# Adapter6.net
KiCad netlist of a schematic drawn in EAGLE
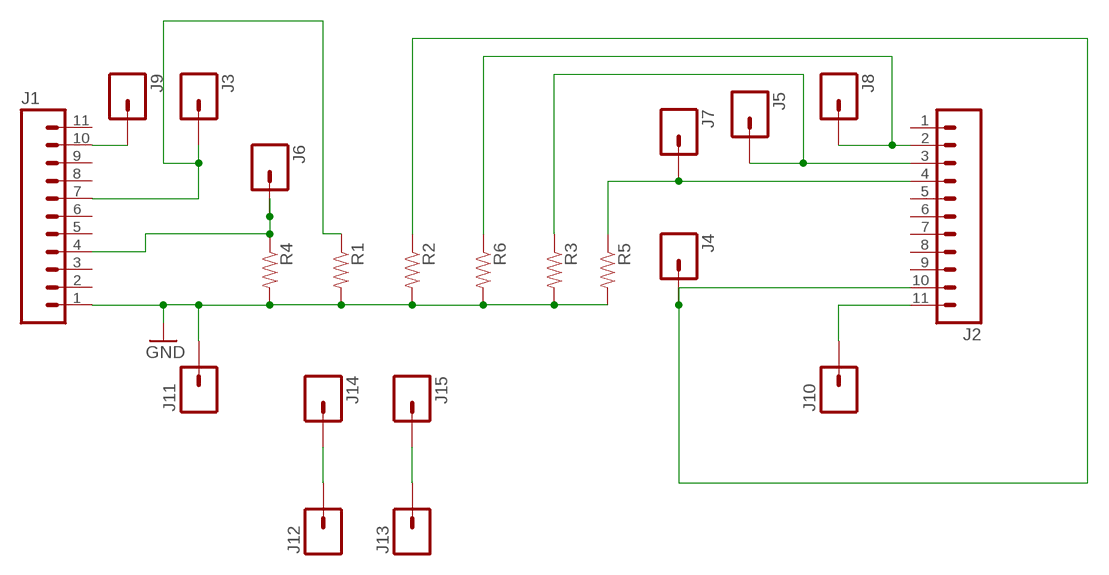
[diagram p0: schematic, sheet 1]

(export (version "E")
  (design (tool "Eeschema 10.0.6"))
  (components
    (comp (ref "J1")
      (value "M11PTH")
      (footprint "eagle-import:1X11")
      (libsource (lib "eagle-import") (part "M11PTH"))
    )
    (comp (ref "J2")
      (value "M11PTH")
      (footprint "eagle-import:1X11")
      (libsource (lib "eagle-import") (part "M11PTH"))
    )
    (comp (ref "J3")
      (value "M01PTH_2MM")
      (footprint "eagle-import:1X01_2MM")
      (libsource (lib "eagle-import") (part "M01PTH_2MM"))
    )
    (comp (ref "J4")
      (value "M01PTH_2MM")
      (footprint "eagle-import:1X01_2MM")
      (libsource (lib "eagle-import") (part "M01PTH_2MM"))
    )
    (comp (ref "J5")
      (value "M01PTH_2MM")
      (footprint "eagle-import:1X01_2MM")
      (libsource (lib "eagle-import") (part "M01PTH_2MM"))
    )
    (comp (ref "J6")
      (value "M01PTH_2MM")
      (footprint "eagle-import:1X01_2MM")
      (libsource (lib "eagle-import") (part "M01PTH_2MM"))
    )
    (comp (ref "J7")
      (value "M01PTH_2MM")
      (footprint "eagle-import:1X01_2MM")
      (libsource (lib "eagle-import") (part "M01PTH_2MM"))
    )
    (comp (ref "J8")
      (value "M01PTH_2MM")
      (footprint "eagle-import:1X01_2MM")
      (libsource (lib "eagle-import") (part "M01PTH_2MM"))
    )
    (comp (ref "J9")
      (value "M01PTH_2MM")
      (footprint "eagle-import:1X01_2MM")
      (libsource (lib "eagle-import") (part "M01PTH_2MM"))
    )
    (comp (ref "J10")
      (value "M01PTH_NO_SILK_YES_STOP")
      (footprint "eagle-import:1X01_NO_SILK")
      (libsource (lib "eagle-import") (part "M01PTH_NO_SILK_YES_STOP"))
    )
    (comp (ref "J11")
      (value "M01PTH_NO_SILK_YES_STOP")
      (footprint "eagle-import:1X01_NO_SILK")
      (libsource (lib "eagle-import") (part "M01PTH_NO_SILK_YES_STOP"))
    )
    (comp (ref "J12")
      (value "M01PTH_2MM")
      (footprint "eagle-import:1X01_2MM")
      (libsource (lib "eagle-import") (part "M01PTH_2MM"))
    )
    (comp (ref "J13")
      (value "M01PTH_2MM")
      (footprint "eagle-import:1X01_2MM")
      (libsource (lib "eagle-import") (part "M01PTH_2MM"))
    )
    (comp (ref "J14")
      (value "M01PTH_NO_SILK_YES_STOP")
      (footprint "eagle-import:1X01_NO_SILK")
      (libsource (lib "eagle-import") (part "M01PTH_NO_SILK_YES_STOP"))
    )
    (comp (ref "J15")
      (value "M01PTH_NO_SILK_YES_STOP")
      (footprint "eagle-import:1X01_NO_SILK")
      (libsource (lib "eagle-import") (part "M01PTH_NO_SILK_YES_STOP"))
    )
    (comp (ref "R1")
      (value "RESISTOR1206")
      (footprint "eagle-import:1206")
      (libsource (lib "eagle-import") (part "RESISTOR1206"))
    )
    (comp (ref "R2")
      (value "RESISTOR1206")
      (footprint "eagle-import:1206")
      (libsource (lib "eagle-import") (part "RESISTOR1206"))
    )
    (comp (ref "R3")
      (value "RESISTOR1206")
      (footprint "eagle-import:1206")
      (libsource (lib "eagle-import") (part "RESISTOR1206"))
    )
    (comp (ref "R4")
      (value "RESISTOR1206")
      (footprint "eagle-import:1206")
      (libsource (lib "eagle-import") (part "RESISTOR1206"))
    )
    (comp (ref "R5")
      (value "RESISTOR1206")
      (footprint "eagle-import:1206")
      (libsource (lib "eagle-import") (part "RESISTOR1206"))
    )
    (comp (ref "R6")
      (value "RESISTOR1206")
      (footprint "eagle-import:1206")
      (libsource (lib "eagle-import") (part "RESISTOR1206"))
    )
  )
  (nets
    (net (code "1") (name "GND") (class "Default")
      (node (ref "J1") (pin "1") (pinfunction "1_1") (pintype "passive"))
      (node (ref "J11") (pin "1") (pinfunction "1_1") (pintype "passive"))
      (node (ref "R1") (pin "2") (pinfunction "2_2") (pintype "passive"))
      (node (ref "R2") (pin "2") (pinfunction "2_2") (pintype "passive"))
      (node (ref "R3") (pin "2") (pinfunction "2_2") (pintype "passive"))
      (node (ref "R4") (pin "2") (pinfunction "2_2") (pintype "passive"))
      (node (ref "R5") (pin "2") (pinfunction "2_2") (pintype "passive"))
      (node (ref "R6") (pin "2") (pinfunction "2_2") (pintype "passive"))
    )
    (net (code "2") (name "Net-(J1-Pad4)") (class "Default")
      (node (ref "J1") (pin "4") (pinfunction "4_4") (pintype "passive"))
      (node (ref "J6") (pin "1") (pinfunction "1_1") (pintype "passive"))
      (node (ref "R4") (pin "1") (pinfunction "1_1") (pintype "passive"))
    )
    (net (code "3") (name "Net-(J1-Pad7)") (class "Default")
      (node (ref "J1") (pin "7") (pinfunction "7_7") (pintype "passive"))
      (node (ref "J3") (pin "1") (pinfunction "1_1") (pintype "passive"))
      (node (ref "R1") (pin "1") (pinfunction "1_1") (pintype "passive"))
    )
    (net (code "4") (name "Net-(J1-Pad10)") (class "Default")
      (node (ref "J1") (pin "10") (pinfunction "10_10") (pintype "passive"))
      (node (ref "J9") (pin "1") (pinfunction "1_1") (pintype "passive"))
    )
    (net (code "5") (name "Net-(J2-Pad2)") (class "Default")
      (node (ref "J2") (pin "2") (pinfunction "2_2") (pintype "passive"))
      (node (ref "J8") (pin "1") (pinfunction "1_1") (pintype "passive"))
      (node (ref "R6") (pin "1") (pinfunction "1_1") (pintype "passive"))
    )
    (net (code "6") (name "Net-(J2-Pad3)") (class "Default")
      (node (ref "J2") (pin "3") (pinfunction "3_3") (pintype "passive"))
      (node (ref "J5") (pin "1") (pinfunction "1_1") (pintype "passive"))
      (node (ref "R3") (pin "1") (pinfunction "1_1") (pintype "passive"))
    )
    (net (code "7") (name "Net-(J2-Pad4)") (class "Default")
      (node (ref "J2") (pin "4") (pinfunction "4_4") (pintype "passive"))
      (node (ref "J7") (pin "1") (pinfunction "1_1") (pintype "passive"))
      (node (ref "R5") (pin "1") (pinfunction "1_1") (pintype "passive"))
    )
    (net (code "8") (name "Net-(J2-Pad10)") (class "Default")
      (node (ref "J2") (pin "10") (pinfunction "10_10") (pintype "passive"))
      (node (ref "J4") (pin "1") (pinfunction "1_1") (pintype "passive"))
      (node (ref "R2") (pin "1") (pinfunction "1_1") (pintype "passive"))
    )
    (net (code "9") (name "Net-(J10-Pad1)") (class "Default")
      (node (ref "J10") (pin "1") (pinfunction "1_1") (pintype "passive"))
      (node (ref "J2") (pin "11") (pinfunction "11_11") (pintype "passive"))
    )
    (net (code "10") (name "Net-(J12-Pad1)") (class "Default")
      (node (ref "J12") (pin "1") (pinfunction "1_1") (pintype "passive"))
      (node (ref "J14") (pin "1") (pinfunction "1_1") (pintype "passive"))
    )
    (net (code "11") (name "Net-(J13-Pad1)") (class "Default")
      (node (ref "J13") (pin "1") (pinfunction "1_1") (pintype "passive"))
      (node (ref "J15") (pin "1") (pinfunction "1_1") (pintype "passive"))
    )
    (net (code "12") (name "unconnected-(J1-Pad2)") (class "Default")
      (node (ref "J1") (pin "2") (pinfunction "2_2") (pintype "passive"))
    )
    (net (code "13") (name "unconnected-(J1-Pad3)") (class "Default")
      (node (ref "J1") (pin "3") (pinfunction "3_3") (pintype "passive"))
    )
    (net (code "14") (name "unconnected-(J1-Pad5)") (class "Default")
      (node (ref "J1") (pin "5") (pinfunction "5_5") (pintype "passive"))
    )
    (net (code "15") (name "unconnected-(J1-Pad6)") (class "Default")
      (node (ref "J1") (pin "6") (pinfunction "6_6") (pintype "passive"))
    )
    (net (code "16") (name "unconnected-(J1-Pad8)") (class "Default")
      (node (ref "J1") (pin "8") (pinfunction "8_8") (pintype "passive"))
    )
    (net (code "17") (name "unconnected-(J1-Pad9)") (class "Default")
      (node (ref "J1") (pin "9") (pinfunction "9_9") (pintype "passive"))
    )
    (net (code "18") (name "unconnected-(J1-Pad11)") (class "Default")
      (node (ref "J1") (pin "11") (pinfunction "11_11") (pintype "passive"))
    )
    (net (code "19") (name "unconnected-(J2-Pad1)") (class "Default")
      (node (ref "J2") (pin "1") (pinfunction "1_1") (pintype "passive"))
    )
    (net (code "20") (name "unconnected-(J2-Pad5)") (class "Default")
      (node (ref "J2") (pin "5") (pinfunction "5_5") (pintype "passive"))
    )
    (net (code "21") (name "unconnected-(J2-Pad6)") (class "Default")
      (node (ref "J2") (pin "6") (pinfunction "6_6") (pintype "passive"))
    )
    (net (code "22") (name "unconnected-(J2-Pad7)") (class "Default")
      (node (ref "J2") (pin "7") (pinfunction "7_7") (pintype "passive"))
    )
    (net (code "23") (name "unconnected-(J2-Pad8)") (class "Default")
      (node (ref "J2") (pin "8") (pinfunction "8_8") (pintype "passive"))
    )
    (net (code "24") (name "unconnected-(J2-Pad9)") (class "Default")
      (node (ref "J2") (pin "9") (pinfunction "9_9") (pintype "passive"))
    )
  )
)
